# devil.net
KiCad netlist of a schematic drawn in EAGLE
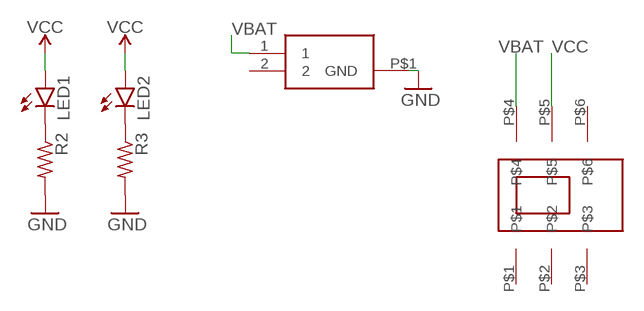
[diagram p0: schematic, sheet 1]

(export (version "E")
  (design (tool "Eeschema 10.0.6"))
  (components
    (comp (ref "LED1")
      (value "LEDCHIP-LED0603")
      (footprint "eagle-import:CHIP-LED0603")
      (libsource (lib "eagle-import") (part "LEDCHIP-LED0603"))
    )
    (comp (ref "LED2")
      (value "LEDCHIP-LED0603")
      (footprint "eagle-import:CHIP-LED0603")
      (libsource (lib "eagle-import") (part "LEDCHIP-LED0603"))
    )
    (comp (ref "R2")
      (value "R-US_R0603")
      (footprint "eagle-import:R0603")
      (libsource (lib "eagle-import") (part "R-US_R0603"))
    )
    (comp (ref "R3")
      (value "R-US_R0603")
      (footprint "eagle-import:R0603")
      (libsource (lib "eagle-import") (part "R-US_R0603"))
    )
    (comp (ref "U$1")
      (value "CL-SB-22A-02T-SLIDE-SWITCH-TUCKED-PADS")
      (footprint "eagle-import:CL-SB-22A-02T-DPDT-COMPACT-SWITCH")
      (libsource (lib "eagle-import") (part "CL-SB-22A-02T-SLIDE-SWITCH-TUCKED-PADS"))
    )
    (comp (ref "VBAT")
      (value "BAT-HLD-012-SMT")
      (footprint "eagle-import:BATHLD012SMT")
      (fields (field (name "MOUSER_PART_NUMBER") "712-BAT-HLD-012-SMT"))
      (libsource (lib "eagle-import") (part "BAT-HLD-012-SMT"))
    )
  )
  (nets
    (net (code "1") (name "/VBAT") (class "Default")
      (node (ref "U$1") (pin "P$4") (pinfunction "P$4_P$4") (pintype "bidirectional"))
      (node (ref "VBAT") (pin "1") (pinfunction "1_1") (pintype "bidirectional"))
    )
    (net (code "2") (name "GND") (class "Default")
      (node (ref "R2") (pin "2") (pinfunction "2_2") (pintype "passive"))
      (node (ref "R3") (pin "2") (pinfunction "2_2") (pintype "passive"))
      (node (ref "VBAT") (pin "P$1") (pinfunction "GND_P$1") (pintype "bidirectional"))
    )
    (net (code "3") (name "Net-(LED1-PadC)") (class "Default")
      (node (ref "LED1") (pin "C") (pinfunction "C_C") (pintype "passive"))
      (node (ref "R2") (pin "1") (pinfunction "1_1") (pintype "passive"))
    )
    (net (code "4") (name "Net-(LED2-PadC)") (class "Default")
      (node (ref "LED2") (pin "C") (pinfunction "C_C") (pintype "passive"))
      (node (ref "R3") (pin "1") (pinfunction "1_1") (pintype "passive"))
    )
    (net (code "5") (name "VCC") (class "Default")
      (node (ref "LED1") (pin "A") (pinfunction "A_A") (pintype "passive"))
      (node (ref "LED2") (pin "A") (pinfunction "A_A") (pintype "passive"))
      (node (ref "U$1") (pin "P$5") (pinfunction "P$5_P$5") (pintype "bidirectional"))
    )
    (net (code "6") (name "unconnected-(U$1-PadP$1)") (class "Default")
      (node (ref "U$1") (pin "P$1") (pinfunction "P$1_P$1") (pintype "bidirectional"))
    )
    (net (code "7") (name "unconnected-(U$1-PadP$2)") (class "Default")
      (node (ref "U$1") (pin "P$2") (pinfunction "P$2_P$2") (pintype "bidirectional"))
    )
    (net (code "8") (name "unconnected-(U$1-PadP$3)") (class "Default")
      (node (ref "U$1") (pin "P$3") (pinfunction "P$3_P$3") (pintype "bidirectional"))
    )
    (net (code "9") (name "unconnected-(U$1-PadP$6)") (class "Default")
      (node (ref "U$1") (pin "P$6") (pinfunction "P$6_P$6") (pintype "bidirectional"))
    )
    (net (code "10") (name "unconnected-(VBAT-Pad2)") (class "Default")
      (node (ref "VBAT") (pin "2") (pinfunction "2_2") (pintype "bidirectional"))
    )
  )
)
